# Safety_2019_V_3_0_Connector_Filter.net
KiCad netlist of a schematic drawn in Altium Designer
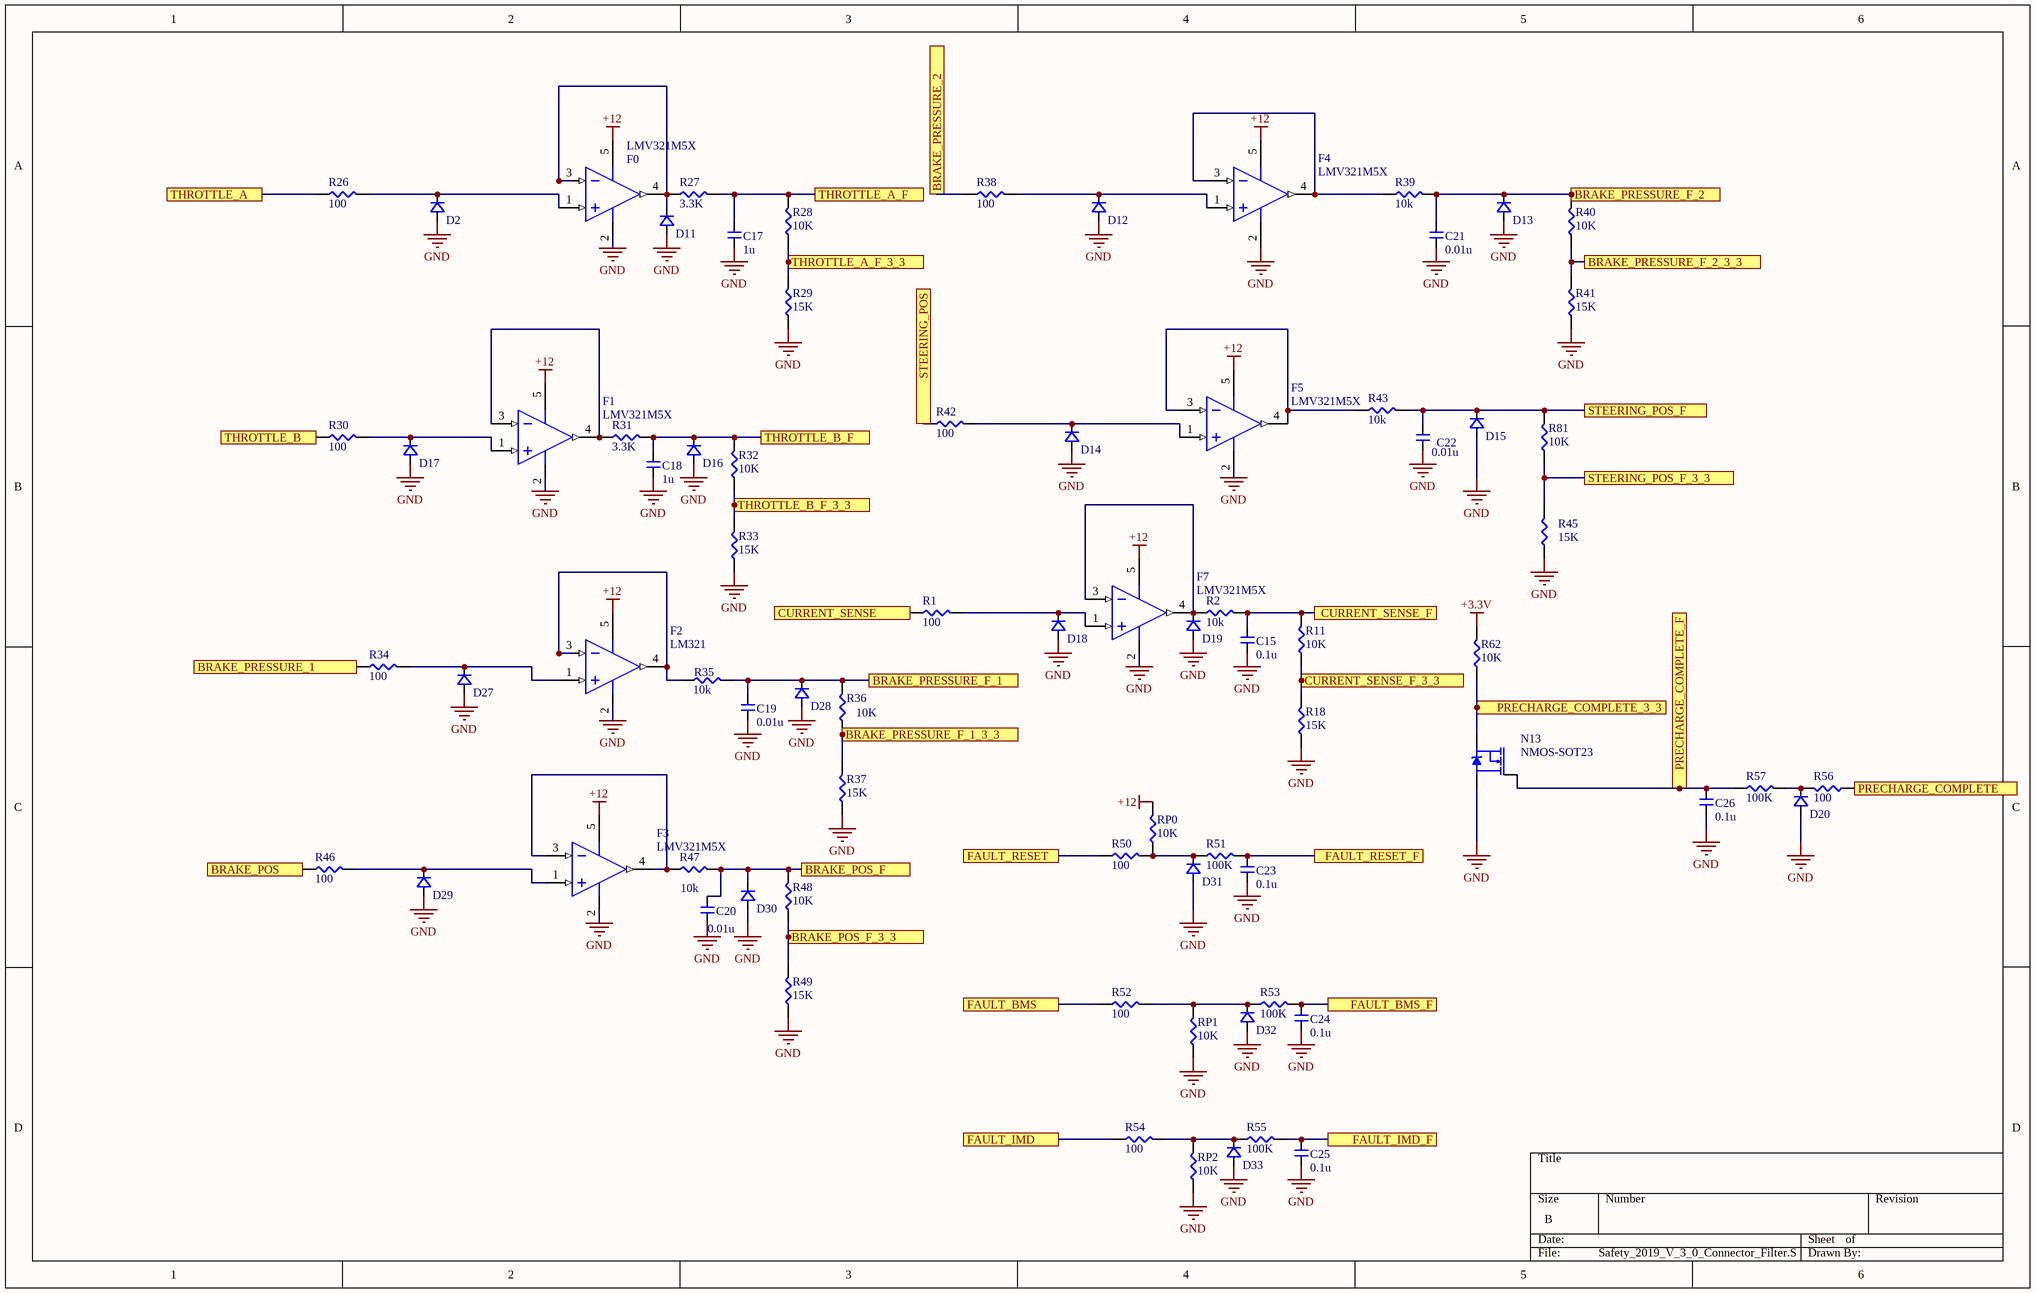
[diagram p0: Safety_2019_V_3_0_Connector_Filter.SchDoc]

(export (version "E")
  (design (tool "Eeschema 10.0.6"))
  (components
    (comp (ref "C15")
      (value "0.1u")
      (footprint "CAP-0603")
      (libsource (lib "ife19_Elec_Library") (part "CAP-0603"))
    )
    (comp (ref "C17")
      (value "1u")
      (footprint "CAP-0603")
      (libsource (lib "ife19_Elec_Library") (part "CAP-0603"))
    )
    (comp (ref "C18")
      (value "1u")
      (footprint "CAP-0603")
      (libsource (lib "ife19_Elec_Library") (part "CAP-0603"))
    )
    (comp (ref "C19")
      (value "0.01u")
      (footprint "CAP-0603")
      (libsource (lib "ife19_Elec_Library") (part "CAP-0603"))
    )
    (comp (ref "C20")
      (value "0.01u")
      (footprint "CAP-0603")
      (libsource (lib "ife19_Elec_Library") (part "CAP-0603"))
    )
    (comp (ref "C21")
      (value "0.01u")
      (footprint "CAP-0603")
      (libsource (lib "ife19_Elec_Library") (part "CAP-0603"))
    )
    (comp (ref "C22")
      (value "0.01u")
      (footprint "CAP-0603")
      (libsource (lib "ife19_Elec_Library") (part "CAP-0603"))
    )
    (comp (ref "C23")
      (value "0.1u")
      (footprint "CAP-0603")
      (libsource (lib "ife19_Elec_Library") (part "CAP-0603"))
    )
    (comp (ref "C24")
      (value "0.1u")
      (footprint "CAP-0603")
      (libsource (lib "ife19_Elec_Library") (part "CAP-0603"))
    )
    (comp (ref "C25")
      (value "0.1u")
      (footprint "CAP-0603")
      (libsource (lib "ife19_Elec_Library") (part "CAP-0603"))
    )
    (comp (ref "C26")
      (value "0.1u")
      (footprint "CAP-0603")
      (libsource (lib "ife19_Elec_Library") (part "CAP-0603"))
    )
    (comp (ref "D2")
      (value "?")
      (footprint "SOD123")
      (libsource (lib "ife19_Elec_Library") (part "DIODE-SOD123"))
    )
    (comp (ref "D11")
      (value "?")
      (footprint "SOD123")
      (libsource (lib "ife19_Elec_Library") (part "DIODE-SOD123"))
    )
    (comp (ref "D12")
      (value "?")
      (footprint "SOD123")
      (libsource (lib "ife19_Elec_Library") (part "DIODE-SOD123"))
    )
    (comp (ref "D13")
      (value "?")
      (footprint "SOD123")
      (libsource (lib "ife19_Elec_Library") (part "DIODE-SOD123"))
    )
    (comp (ref "D14")
      (value "?")
      (footprint "SOD123")
      (libsource (lib "ife19_Elec_Library") (part "DIODE-SOD123"))
    )
    (comp (ref "D15")
      (value "?")
      (footprint "SOD123")
      (libsource (lib "ife19_Elec_Library") (part "DIODE-SOD123"))
    )
    (comp (ref "D16")
      (value "?")
      (footprint "SOD123")
      (libsource (lib "ife19_Elec_Library") (part "DIODE-SOD123"))
    )
    (comp (ref "D17")
      (value "?")
      (footprint "SOD123")
      (libsource (lib "ife19_Elec_Library") (part "DIODE-SOD123"))
    )
    (comp (ref "D18")
      (value "?")
      (footprint "SOD123")
      (libsource (lib "ife19_Elec_Library") (part "DIODE-SOD123"))
    )
    (comp (ref "D19")
      (value "?")
      (footprint "SOD123")
      (libsource (lib "ife19_Elec_Library") (part "DIODE-SOD123"))
    )
    (comp (ref "D20")
      (value "12V ZENER")
      (footprint "SOD123")
      (libsource (lib "ife19_Elec_Library") (part "DIODE-SOD123"))
    )
    (comp (ref "D27")
      (value "?")
      (footprint "SOD123")
      (libsource (lib "ife19_Elec_Library") (part "DIODE-SOD123"))
    )
    (comp (ref "D28")
      (value "?")
      (footprint "SOD123")
      (libsource (lib "ife19_Elec_Library") (part "DIODE-SOD123"))
    )
    (comp (ref "D29")
      (value "?")
      (footprint "SOD123")
      (libsource (lib "ife19_Elec_Library") (part "DIODE-SOD123"))
    )
    (comp (ref "D30")
      (value "?")
      (footprint "SOD123")
      (libsource (lib "ife19_Elec_Library") (part "DIODE-SOD123"))
    )
    (comp (ref "D31")
      (value "12V ZENER")
      (footprint "SOD123")
      (libsource (lib "ife19_Elec_Library") (part "DIODE-SOD123"))
    )
    (comp (ref "D32")
      (value "12V ZENER")
      (footprint "SOD123")
      (libsource (lib "ife19_Elec_Library") (part "DIODE-SOD123"))
    )
    (comp (ref "D33")
      (value "12V ZENER")
      (footprint "SOD123")
      (libsource (lib "ife19_Elec_Library") (part "DIODE-SOD123"))
    )
    (comp (ref "F0")
      (value "LMV321M5X")
      (footprint "MF05A_N")
      (description "General Purpose, Low Voltage, Rail-to-Rail Output Operational Amplifiers, 5-pin SOT-23")
      (fields (field (name "MANUFACTURER") "National Semiconductor"))
      (libsource (lib "Altium Content Vault") (part "AMP-OPA-LMV551-5"))
    )
    (comp (ref "F1")
      (value "LMV321M5X")
      (footprint "MF05A_N")
      (description "General Purpose, Low Voltage, Rail-to-Rail Output Operational Amplifiers, 5-pin SOT-23")
      (fields (field (name "MANUFACTURER") "National Semiconductor"))
      (libsource (lib "Altium Content Vault") (part "AMP-OPA-LMV551-5"))
    )
    (comp (ref "F2")
      (value "LM321")
      (footprint "MF05A_N")
      (description "General Purpose, Low Voltage, Rail-to-Rail Output Operational Amplifiers, 5-pin SOT-23")
      (fields (field (name "MANUFACTURER") "National Semiconductor"))
      (libsource (lib "Altium Content Vault") (part "AMP-OPA-LMV551-5"))
    )
    (comp (ref "F3")
      (value "LMV321M5X")
      (footprint "MF05A_N")
      (description "General Purpose, Low Voltage, Rail-to-Rail Output Operational Amplifiers, 5-pin SOT-23")
      (fields (field (name "MANUFACTURER") "National Semiconductor"))
      (libsource (lib "Altium Content Vault") (part "AMP-OPA-LMV551-5"))
    )
    (comp (ref "F4")
      (value "LMV321M5X")
      (footprint "MF05A_N")
      (description "General Purpose, Low Voltage, Rail-to-Rail Output Operational Amplifiers, 5-pin SOT-23")
      (fields (field (name "MANUFACTURER") "National Semiconductor"))
      (libsource (lib "Altium Content Vault") (part "AMP-OPA-LMV551-5"))
    )
    (comp (ref "F5")
      (value "LMV321M5X")
      (footprint "MF05A_N")
      (description "General Purpose, Low Voltage, Rail-to-Rail Output Operational Amplifiers, 5-pin SOT-23")
      (fields (field (name "MANUFACTURER") "National Semiconductor"))
      (libsource (lib "Altium Content Vault") (part "AMP-OPA-LMV551-5"))
    )
    (comp (ref "F7")
      (value "LMV321M5X")
      (footprint "MF05A_N")
      (description "General Purpose, Low Voltage, Rail-to-Rail Output Operational Amplifiers, 5-pin SOT-23")
      (fields (field (name "MANUFACTURER") "National Semiconductor"))
      (libsource (lib "Altium Content Vault") (part "AMP-OPA-LMV551-5"))
    )
    (comp (ref "N13")
      (value "NMOS-SOT23")
      (footprint "SOT23")
      (libsource (lib "ife19_Elec_Library") (part "NMOS-SOT23"))
    )
    (comp (ref "R1")
      (value "100")
      (footprint "RES-0603")
      (libsource (lib "ife19_Elec_Library") (part "RES-0603"))
    )
    (comp (ref "R2")
      (value "10k")
      (footprint "RES-0603")
      (libsource (lib "ife19_Elec_Library") (part "RES-0603"))
    )
    (comp (ref "R11")
      (value "10K")
      (footprint "RES-0603")
      (libsource (lib "ife19_Elec_Library") (part "RES-0603"))
    )
    (comp (ref "R18")
      (value "15K")
      (footprint "RES-0603")
      (libsource (lib "ife19_Elec_Library") (part "RES-0603"))
    )
    (comp (ref "R26")
      (value "100")
      (footprint "RES-0603")
      (libsource (lib "ife19_Elec_Library") (part "RES-0603"))
    )
    (comp (ref "R27")
      (value "3.3K")
      (footprint "RES-0603")
      (libsource (lib "ife19_Elec_Library") (part "RES-0603"))
    )
    (comp (ref "R28")
      (value "10K")
      (footprint "RES-0603")
      (libsource (lib "ife19_Elec_Library") (part "RES-0603"))
    )
    (comp (ref "R29")
      (value "15K")
      (footprint "RES-0603")
      (libsource (lib "ife19_Elec_Library") (part "RES-0603"))
    )
    (comp (ref "R30")
      (value "100")
      (footprint "RES-0603")
      (libsource (lib "ife19_Elec_Library") (part "RES-0603"))
    )
    (comp (ref "R31")
      (value "3.3K")
      (footprint "RES-0603")
      (libsource (lib "ife19_Elec_Library") (part "RES-0603"))
    )
    (comp (ref "R32")
      (value "10K")
      (footprint "RES-0603")
      (libsource (lib "ife19_Elec_Library") (part "RES-0603"))
    )
    (comp (ref "R33")
      (value "15K")
      (footprint "RES-0603")
      (libsource (lib "ife19_Elec_Library") (part "RES-0603"))
    )
    (comp (ref "R34")
      (value "100")
      (footprint "RES-0603")
      (libsource (lib "ife19_Elec_Library") (part "RES-0603"))
    )
    (comp (ref "R35")
      (value "10k")
      (footprint "RES-0603")
      (libsource (lib "ife19_Elec_Library") (part "RES-0603"))
    )
    (comp (ref "R36")
      (value "10K")
      (footprint "RES-0603")
      (libsource (lib "ife19_Elec_Library") (part "RES-0603"))
    )
    (comp (ref "R37")
      (value "15K")
      (footprint "RES-0603")
      (libsource (lib "ife19_Elec_Library") (part "RES-0603"))
    )
    (comp (ref "R38")
      (value "100")
      (footprint "RES-0603")
      (libsource (lib "ife19_Elec_Library") (part "RES-0603"))
    )
    (comp (ref "R39")
      (value "10k")
      (footprint "RES-0603")
      (libsource (lib "ife19_Elec_Library") (part "RES-0603"))
    )
    (comp (ref "R40")
      (value "10K")
      (footprint "RES-0603")
      (libsource (lib "ife19_Elec_Library") (part "RES-0603"))
    )
    (comp (ref "R41")
      (value "15K")
      (footprint "RES-0603")
      (libsource (lib "ife19_Elec_Library") (part "RES-0603"))
    )
    (comp (ref "R42")
      (value "100")
      (footprint "RES-0603")
      (libsource (lib "ife19_Elec_Library") (part "RES-0603"))
    )
    (comp (ref "R43")
      (value "10k")
      (footprint "RES-0603")
      (libsource (lib "ife19_Elec_Library") (part "RES-0603"))
    )
    (comp (ref "R45")
      (value "15K")
      (footprint "RES-0603")
      (libsource (lib "ife19_Elec_Library") (part "RES-0603"))
    )
    (comp (ref "R46")
      (value "100")
      (footprint "RES-0603")
      (libsource (lib "ife19_Elec_Library") (part "RES-0603"))
    )
    (comp (ref "R47")
      (value "10k")
      (footprint "RES-0603")
      (libsource (lib "ife19_Elec_Library") (part "RES-0603"))
    )
    (comp (ref "R48")
      (value "10K")
      (footprint "RES-0603")
      (libsource (lib "ife19_Elec_Library") (part "RES-0603"))
    )
    (comp (ref "R49")
      (value "15K")
      (footprint "RES-0603")
      (libsource (lib "ife19_Elec_Library") (part "RES-0603"))
    )
    (comp (ref "R50")
      (value "100")
      (footprint "RES-0603")
      (libsource (lib "ife19_Elec_Library") (part "RES-0603"))
    )
    (comp (ref "R51")
      (value "100K")
      (footprint "RES-0603")
      (libsource (lib "ife19_Elec_Library") (part "RES-0603"))
    )
    (comp (ref "R52")
      (value "100")
      (footprint "RES-0603")
      (libsource (lib "ife19_Elec_Library") (part "RES-0603"))
    )
    (comp (ref "R53")
      (value "100K")
      (footprint "RES-0603")
      (libsource (lib "ife19_Elec_Library") (part "RES-0603"))
    )
    (comp (ref "R54")
      (value "100")
      (footprint "RES-0603")
      (libsource (lib "ife19_Elec_Library") (part "RES-0603"))
    )
    (comp (ref "R55")
      (value "100K")
      (footprint "RES-0603")
      (libsource (lib "ife19_Elec_Library") (part "RES-0603"))
    )
    (comp (ref "R56")
      (value "100")
      (footprint "RES-0603")
      (libsource (lib "ife19_Elec_Library") (part "RES-0603"))
    )
    (comp (ref "R57")
      (value "100K")
      (footprint "RES-0603")
      (libsource (lib "ife19_Elec_Library") (part "RES-0603"))
    )
    (comp (ref "R62")
      (value "10K")
      (footprint "RES-0603")
      (libsource (lib "ife19_Elec_Library") (part "RES-0603"))
    )
    (comp (ref "R81")
      (value "10K")
      (footprint "RES-0603")
      (libsource (lib "ife19_Elec_Library") (part "RES-0603"))
    )
    (comp (ref "RP0")
      (value "10K")
      (footprint "RES-0603")
      (libsource (lib "ife19_Elec_Library") (part "RES-0603"))
    )
    (comp (ref "RP1")
      (value "10K")
      (footprint "RES-0603")
      (libsource (lib "ife19_Elec_Library") (part "RES-0603"))
    )
    (comp (ref "RP2")
      (value "10K")
      (footprint "RES-0603")
      (libsource (lib "ife19_Elec_Library") (part "RES-0603"))
    )
  )
  (nets
    (net (code "1") (name "+3.3V") (class "Default")
      (node (ref "R62") (pin "2") (pinfunction "2_2") (pintype "passive"))
    )
    (net (code "2") (name "+12") (class "Default")
      (node (ref "F0") (pin "5") (pinfunction "V+_5") (pintype "power_in"))
      (node (ref "F1") (pin "5") (pinfunction "V+_5") (pintype "power_in"))
      (node (ref "F2") (pin "5") (pinfunction "V+_5") (pintype "power_in"))
      (node (ref "F3") (pin "5") (pinfunction "V+_5") (pintype "power_in"))
      (node (ref "F4") (pin "5") (pinfunction "V+_5") (pintype "power_in"))
      (node (ref "F5") (pin "5") (pinfunction "V+_5") (pintype "power_in"))
      (node (ref "F7") (pin "5") (pinfunction "V+_5") (pintype "power_in"))
      (node (ref "RP0") (pin "2") (pinfunction "2_2") (pintype "passive"))
    )
    (net (code "3") (name "/BRAKE_POS") (class "Default")
      (node (ref "R46") (pin "1") (pinfunction "1_1") (pintype "passive"))
    )
    (net (code "4") (name "/BRAKE_POS_F") (class "Default")
      (node (ref "C20") (pin "1") (pinfunction "1_1") (pintype "passive"))
      (node (ref "D30") (pin "K") (pinfunction "K_K") (pintype "passive"))
      (node (ref "R47") (pin "2") (pinfunction "2_2") (pintype "passive"))
      (node (ref "R48") (pin "2") (pinfunction "2_2") (pintype "passive"))
    )
    (net (code "5") (name "/BRAKE_POS_F_3_3") (class "Default")
      (node (ref "R48") (pin "1") (pinfunction "1_1") (pintype "passive"))
      (node (ref "R49") (pin "2") (pinfunction "2_2") (pintype "passive"))
    )
    (net (code "6") (name "/BRAKE_PRESSURE_1") (class "Default")
      (node (ref "R34") (pin "1") (pinfunction "1_1") (pintype "passive"))
    )
    (net (code "7") (name "/BRAKE_PRESSURE_2") (class "Default")
      (node (ref "R38") (pin "1") (pinfunction "1_1") (pintype "passive"))
    )
    (net (code "8") (name "/BRAKE_PRESSURE_F_1") (class "Default")
      (node (ref "C19") (pin "1") (pinfunction "1_1") (pintype "passive"))
      (node (ref "D28") (pin "K") (pinfunction "K_K") (pintype "passive"))
      (node (ref "R35") (pin "2") (pinfunction "2_2") (pintype "passive"))
      (node (ref "R36") (pin "2") (pinfunction "2_2") (pintype "passive"))
    )
    (net (code "9") (name "/BRAKE_PRESSURE_F_1_3_3") (class "Default")
      (node (ref "R36") (pin "1") (pinfunction "1_1") (pintype "passive"))
      (node (ref "R37") (pin "2") (pinfunction "2_2") (pintype "passive"))
    )
    (net (code "10") (name "/BRAKE_PRESSURE_F_2") (class "Default")
      (node (ref "C21") (pin "1") (pinfunction "1_1") (pintype "passive"))
      (node (ref "D13") (pin "K") (pinfunction "K_K") (pintype "passive"))
      (node (ref "R39") (pin "2") (pinfunction "2_2") (pintype "passive"))
      (node (ref "R40") (pin "2") (pinfunction "2_2") (pintype "passive"))
    )
    (net (code "11") (name "/BRAKE_PRESSURE_F_2_3_3") (class "Default")
      (node (ref "R40") (pin "1") (pinfunction "1_1") (pintype "passive"))
      (node (ref "R41") (pin "2") (pinfunction "2_2") (pintype "passive"))
    )
    (net (code "12") (name "/CURRENT_SENSE") (class "Default")
      (node (ref "R1") (pin "1") (pinfunction "1_1") (pintype "passive"))
    )
    (net (code "13") (name "/CURRENT_SENSE_F") (class "Default")
      (node (ref "C15") (pin "1") (pinfunction "1_1") (pintype "passive"))
      (node (ref "R11") (pin "2") (pinfunction "2_2") (pintype "passive"))
      (node (ref "R2") (pin "2") (pinfunction "2_2") (pintype "passive"))
    )
    (net (code "14") (name "/CURRENT_SENSE_F_3_3") (class "Default")
      (node (ref "R11") (pin "1") (pinfunction "1_1") (pintype "passive"))
      (node (ref "R18") (pin "2") (pinfunction "2_2") (pintype "passive"))
    )
    (net (code "15") (name "/FAULT_BMS") (class "Default")
      (node (ref "R52") (pin "1") (pinfunction "1_1") (pintype "passive"))
    )
    (net (code "16") (name "/FAULT_BMS_F") (class "Default")
      (node (ref "C24") (pin "2") (pinfunction "2_2") (pintype "passive"))
      (node (ref "R53") (pin "2") (pinfunction "2_2") (pintype "passive"))
    )
    (net (code "17") (name "/FAULT_IMD") (class "Default")
      (node (ref "R54") (pin "1") (pinfunction "1_1") (pintype "passive"))
    )
    (net (code "18") (name "/FAULT_IMD_F") (class "Default")
      (node (ref "C25") (pin "2") (pinfunction "2_2") (pintype "passive"))
      (node (ref "R55") (pin "2") (pinfunction "2_2") (pintype "passive"))
    )
    (net (code "19") (name "/FAULT_RESET") (class "Default")
      (node (ref "R50") (pin "1") (pinfunction "1_1") (pintype "passive"))
    )
    (net (code "20") (name "/FAULT_RESET_F") (class "Default")
      (node (ref "C23") (pin "2") (pinfunction "2_2") (pintype "passive"))
      (node (ref "R51") (pin "2") (pinfunction "2_2") (pintype "passive"))
    )
    (net (code "21") (name "/PRECHARGE_COMPLETE") (class "Default")
      (node (ref "R56") (pin "1") (pinfunction "1_1") (pintype "passive"))
    )
    (net (code "22") (name "/PRECHARGE_COMPLETE_3_3") (class "Default")
      (node (ref "N13") (pin "3") (pinfunction "D_3") (pintype "passive"))
      (node (ref "R62") (pin "1") (pinfunction "1_1") (pintype "passive"))
    )
    (net (code "23") (name "/PRECHARGE_COMPLETE_F") (class "Default")
      (node (ref "C26") (pin "2") (pinfunction "2_2") (pintype "passive"))
      (node (ref "N13") (pin "1") (pinfunction "G_1") (pintype "passive"))
      (node (ref "R57") (pin "1") (pinfunction "1_1") (pintype "passive"))
    )
    (net (code "24") (name "/STEERING_POS") (class "Default")
      (node (ref "R42") (pin "1") (pinfunction "1_1") (pintype "passive"))
    )
    (net (code "25") (name "/STEERING_POS_F") (class "Default")
      (node (ref "C22") (pin "1") (pinfunction "1_1") (pintype "passive"))
      (node (ref "D15") (pin "K") (pinfunction "K_K") (pintype "passive"))
      (node (ref "R43") (pin "2") (pinfunction "2_2") (pintype "passive"))
      (node (ref "R81") (pin "2") (pinfunction "2_2") (pintype "passive"))
    )
    (net (code "26") (name "/STEERING_POS_F_3_3") (class "Default")
      (node (ref "R45") (pin "2") (pinfunction "2_2") (pintype "passive"))
      (node (ref "R81") (pin "1") (pinfunction "1_1") (pintype "passive"))
    )
    (net (code "27") (name "/THROTTLE_A") (class "Default")
      (node (ref "R26") (pin "1") (pinfunction "1_1") (pintype "passive"))
    )
    (net (code "28") (name "/THROTTLE_A_F") (class "Default")
      (node (ref "C17") (pin "1") (pinfunction "1_1") (pintype "passive"))
      (node (ref "R27") (pin "2") (pinfunction "2_2") (pintype "passive"))
      (node (ref "R28") (pin "2") (pinfunction "2_2") (pintype "passive"))
    )
    (net (code "29") (name "/THROTTLE_A_F_3_3") (class "Default")
      (node (ref "R28") (pin "1") (pinfunction "1_1") (pintype "passive"))
      (node (ref "R29") (pin "2") (pinfunction "2_2") (pintype "passive"))
    )
    (net (code "30") (name "/THROTTLE_B") (class "Default")
      (node (ref "R30") (pin "1") (pinfunction "1_1") (pintype "passive"))
    )
    (net (code "31") (name "/THROTTLE_B_F") (class "Default")
      (node (ref "C18") (pin "1") (pinfunction "1_1") (pintype "passive"))
      (node (ref "D16") (pin "K") (pinfunction "K_K") (pintype "passive"))
      (node (ref "R31") (pin "2") (pinfunction "2_2") (pintype "passive"))
      (node (ref "R32") (pin "2") (pinfunction "2_2") (pintype "passive"))
    )
    (net (code "32") (name "/THROTTLE_B_F_3_3") (class "Default")
      (node (ref "R32") (pin "1") (pinfunction "1_1") (pintype "passive"))
      (node (ref "R33") (pin "2") (pinfunction "2_2") (pintype "passive"))
    )
    (net (code "33") (name "GND") (class "Default")
      (node (ref "C15") (pin "2") (pinfunction "2_2") (pintype "passive"))
      (node (ref "C17") (pin "2") (pinfunction "2_2") (pintype "passive"))
      (node (ref "C18") (pin "2") (pinfunction "2_2") (pintype "passive"))
      (node (ref "C19") (pin "2") (pinfunction "2_2") (pintype "passive"))
      (node (ref "C20") (pin "2") (pinfunction "2_2") (pintype "passive"))
      (node (ref "C21") (pin "2") (pinfunction "2_2") (pintype "passive"))
      (node (ref "C22") (pin "2") (pinfunction "2_2") (pintype "passive"))
      (node (ref "C23") (pin "1") (pinfunction "1_1") (pintype "passive"))
      (node (ref "C24") (pin "1") (pinfunction "1_1") (pintype "passive"))
      (node (ref "C25") (pin "1") (pinfunction "1_1") (pintype "passive"))
      (node (ref "C26") (pin "1") (pinfunction "1_1") (pintype "passive"))
      (node (ref "D11") (pin "A") (pinfunction "A_A") (pintype "passive"))
      (node (ref "D12") (pin "A") (pinfunction "A_A") (pintype "passive"))
      (node (ref "D13") (pin "A") (pinfunction "A_A") (pintype "passive"))
      (node (ref "D14") (pin "A") (pinfunction "A_A") (pintype "passive"))
      (node (ref "D15") (pin "A") (pinfunction "A_A") (pintype "passive"))
      (node (ref "D16") (pin "A") (pinfunction "A_A") (pintype "passive"))
      (node (ref "D17") (pin "A") (pinfunction "A_A") (pintype "passive"))
      (node (ref "D18") (pin "A") (pinfunction "A_A") (pintype "passive"))
      (node (ref "D19") (pin "A") (pinfunction "A_A") (pintype "passive"))
      (node (ref "D2") (pin "A") (pinfunction "A_A") (pintype "passive"))
      (node (ref "D20") (pin "A") (pinfunction "A_A") (pintype "passive"))
      (node (ref "D27") (pin "A") (pinfunction "A_A") (pintype "passive"))
      (node (ref "D28") (pin "A") (pinfunction "A_A") (pintype "passive"))
      (node (ref "D29") (pin "A") (pinfunction "A_A") (pintype "passive"))
      (node (ref "D30") (pin "A") (pinfunction "A_A") (pintype "passive"))
      (node (ref "D31") (pin "A") (pinfunction "A_A") (pintype "passive"))
      (node (ref "D32") (pin "A") (pinfunction "A_A") (pintype "passive"))
      (node (ref "D33") (pin "A") (pinfunction "A_A") (pintype "passive"))
      (node (ref "F0") (pin "2") (pinfunction "V-_2") (pintype "power_in"))
      (node (ref "F1") (pin "2") (pinfunction "V-_2") (pintype "power_in"))
      (node (ref "F2") (pin "2") (pinfunction "V-_2") (pintype "power_in"))
      (node (ref "F3") (pin "2") (pinfunction "V-_2") (pintype "power_in"))
      (node (ref "F4") (pin "2") (pinfunction "V-_2") (pintype "power_in"))
      (node (ref "F5") (pin "2") (pinfunction "V-_2") (pintype "power_in"))
      (node (ref "F7") (pin "2") (pinfunction "V-_2") (pintype "power_in"))
      (node (ref "N13") (pin "2") (pinfunction "S_2") (pintype "passive"))
      (node (ref "R18") (pin "1") (pinfunction "1_1") (pintype "passive"))
      (node (ref "R29") (pin "1") (pinfunction "1_1") (pintype "passive"))
      (node (ref "R33") (pin "1") (pinfunction "1_1") (pintype "passive"))
      (node (ref "R37") (pin "1") (pinfunction "1_1") (pintype "passive"))
      (node (ref "R41") (pin "1") (pinfunction "1_1") (pintype "passive"))
      (node (ref "R45") (pin "1") (pinfunction "1_1") (pintype "passive"))
      (node (ref "R49") (pin "1") (pinfunction "1_1") (pintype "passive"))
      (node (ref "RP1") (pin "1") (pinfunction "1_1") (pintype "passive"))
      (node (ref "RP2") (pin "1") (pinfunction "1_1") (pintype "passive"))
    )
    (net (code "34") (name "Net-(D20-PadK)") (class "Default")
      (node (ref "D20") (pin "K") (pinfunction "K_K") (pintype "passive"))
      (node (ref "R56") (pin "2") (pinfunction "2_2") (pintype "passive"))
      (node (ref "R57") (pin "2") (pinfunction "2_2") (pintype "passive"))
    )
    (net (code "35") (name "Net-(D31-PadK)") (class "Default")
      (node (ref "D31") (pin "K") (pinfunction "K_K") (pintype "passive"))
      (node (ref "R50") (pin "2") (pinfunction "2_2") (pintype "passive"))
      (node (ref "R51") (pin "1") (pinfunction "1_1") (pintype "passive"))
      (node (ref "RP0") (pin "1") (pinfunction "1_1") (pintype "passive"))
    )
    (net (code "36") (name "Net-(D32-PadK)") (class "Default")
      (node (ref "D32") (pin "K") (pinfunction "K_K") (pintype "passive"))
      (node (ref "R52") (pin "2") (pinfunction "2_2") (pintype "passive"))
      (node (ref "R53") (pin "1") (pinfunction "1_1") (pintype "passive"))
      (node (ref "RP1") (pin "2") (pinfunction "2_2") (pintype "passive"))
    )
    (net (code "37") (name "Net-(D33-PadK)") (class "Default")
      (node (ref "D33") (pin "K") (pinfunction "K_K") (pintype "passive"))
      (node (ref "R54") (pin "2") (pinfunction "2_2") (pintype "passive"))
      (node (ref "R55") (pin "1") (pinfunction "1_1") (pintype "passive"))
      (node (ref "RP2") (pin "2") (pinfunction "2_2") (pintype "passive"))
    )
    (net (code "38") (name "Net-(F0-IN+)") (class "Default")
      (node (ref "D2") (pin "K") (pinfunction "K_K") (pintype "passive"))
      (node (ref "F0") (pin "1") (pinfunction "IN+_1") (pintype "input"))
      (node (ref "R26") (pin "2") (pinfunction "2_2") (pintype "passive"))
    )
    (net (code "39") (name "Net-(F0-IN-)") (class "Default")
      (node (ref "D11") (pin "K") (pinfunction "K_K") (pintype "passive"))
      (node (ref "F0") (pin "3") (pinfunction "IN-_3") (pintype "input"))
      (node (ref "F0") (pin "4") (pinfunction "OUT_4") (pintype "output"))
      (node (ref "R27") (pin "1") (pinfunction "1_1") (pintype "passive"))
    )
    (net (code "40") (name "Net-(F1-IN+)") (class "Default")
      (node (ref "D17") (pin "K") (pinfunction "K_K") (pintype "passive"))
      (node (ref "F1") (pin "1") (pinfunction "IN+_1") (pintype "input"))
      (node (ref "R30") (pin "2") (pinfunction "2_2") (pintype "passive"))
    )
    (net (code "41") (name "Net-(F1-IN-)") (class "Default")
      (node (ref "F1") (pin "3") (pinfunction "IN-_3") (pintype "input"))
      (node (ref "F1") (pin "4") (pinfunction "OUT_4") (pintype "output"))
      (node (ref "R31") (pin "1") (pinfunction "1_1") (pintype "passive"))
    )
    (net (code "42") (name "Net-(F2-IN+)") (class "Default")
      (node (ref "D27") (pin "K") (pinfunction "K_K") (pintype "passive"))
      (node (ref "F2") (pin "1") (pinfunction "IN+_1") (pintype "input"))
      (node (ref "R34") (pin "2") (pinfunction "2_2") (pintype "passive"))
    )
    (net (code "43") (name "Net-(F2-IN-)") (class "Default")
      (node (ref "F2") (pin "3") (pinfunction "IN-_3") (pintype "input"))
      (node (ref "F2") (pin "4") (pinfunction "OUT_4") (pintype "output"))
      (node (ref "R35") (pin "1") (pinfunction "1_1") (pintype "passive"))
    )
    (net (code "44") (name "Net-(F3-IN+)") (class "Default")
      (node (ref "D29") (pin "K") (pinfunction "K_K") (pintype "passive"))
      (node (ref "F3") (pin "1") (pinfunction "IN+_1") (pintype "input"))
      (node (ref "R46") (pin "2") (pinfunction "2_2") (pintype "passive"))
    )
    (net (code "45") (name "Net-(F3-IN-)") (class "Default")
      (node (ref "F3") (pin "3") (pinfunction "IN-_3") (pintype "input"))
      (node (ref "F3") (pin "4") (pinfunction "OUT_4") (pintype "output"))
      (node (ref "R47") (pin "1") (pinfunction "1_1") (pintype "passive"))
    )
    (net (code "46") (name "Net-(F4-IN+)") (class "Default")
      (node (ref "D12") (pin "K") (pinfunction "K_K") (pintype "passive"))
      (node (ref "F4") (pin "1") (pinfunction "IN+_1") (pintype "input"))
      (node (ref "R38") (pin "2") (pinfunction "2_2") (pintype "passive"))
    )
    (net (code "47") (name "Net-(F4-IN-)") (class "Default")
      (node (ref "F4") (pin "3") (pinfunction "IN-_3") (pintype "input"))
      (node (ref "F4") (pin "4") (pinfunction "OUT_4") (pintype "output"))
      (node (ref "R39") (pin "1") (pinfunction "1_1") (pintype "passive"))
    )
    (net (code "48") (name "Net-(F5-IN+)") (class "Default")
      (node (ref "D14") (pin "K") (pinfunction "K_K") (pintype "passive"))
      (node (ref "F5") (pin "1") (pinfunction "IN+_1") (pintype "input"))
      (node (ref "R42") (pin "2") (pinfunction "2_2") (pintype "passive"))
    )
    (net (code "49") (name "Net-(F5-IN-)") (class "Default")
      (node (ref "F5") (pin "3") (pinfunction "IN-_3") (pintype "input"))
      (node (ref "F5") (pin "4") (pinfunction "OUT_4") (pintype "output"))
      (node (ref "R43") (pin "1") (pinfunction "1_1") (pintype "passive"))
    )
    (net (code "50") (name "Net-(F7-IN+)") (class "Default")
      (node (ref "D18") (pin "K") (pinfunction "K_K") (pintype "passive"))
      (node (ref "F7") (pin "1") (pinfunction "IN+_1") (pintype "input"))
      (node (ref "R1") (pin "2") (pinfunction "2_2") (pintype "passive"))
    )
    (net (code "51") (name "Net-(F7-IN-)") (class "Default")
      (node (ref "D19") (pin "K") (pinfunction "K_K") (pintype "passive"))
      (node (ref "F7") (pin "3") (pinfunction "IN-_3") (pintype "input"))
      (node (ref "F7") (pin "4") (pinfunction "OUT_4") (pintype "output"))
      (node (ref "R2") (pin "1") (pinfunction "1_1") (pintype "passive"))
    )
  )
)
